# CONNECTOR.net
KiCad netlist of a schematic drawn in Altium Designer
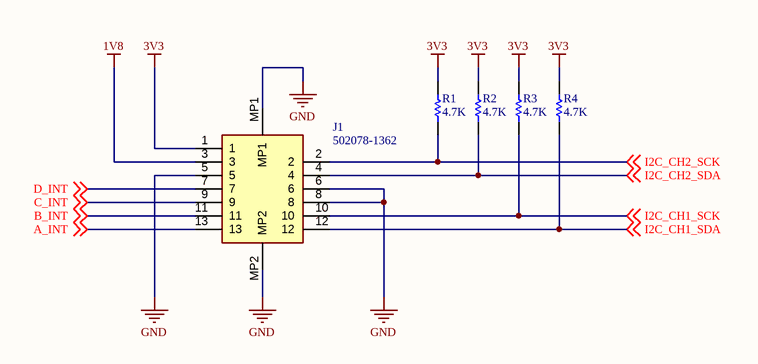
[diagram p0: CONNECTOR.SchDoc]

(export (version "E")
  (design (tool "Eeschema 10.0.6"))
  (components
    (comp (ref "J1")
      (value "502078-1362")
      (footprint "SamacSys:5020781362")
      (description "Connector")
      (fields (field (name "MOUSER PART NUMBER") "538-502078-1362"))
      (libsource (lib "*") (part "502078-1362"))
    )
    (comp (ref "R1")
      (value "4.7K")
      (footprint "RESC1005X40X25LL05T05")
      (description "Chip Resistor, 4.7 KOhm, +/- 1%, 0.1 W, -55 to 155 degC, 0402 (1005 Metric), RoHS, Tape and Reel")
      (fields (field (name "TOLERANCE") "1%") (field (name "PARTNUMBER") "ERJ-2RKF4701X"))
      (libsource (lib "Altium Content Vault") (part "RES-2"))
    )
    (comp (ref "R2")
      (value "4.7K")
      (footprint "RESC1005X40X25LL05T05")
      (description "Chip Resistor, 4.7 KOhm, +/- 1%, 0.1 W, -55 to 155 degC, 0402 (1005 Metric), RoHS, Tape and Reel")
      (fields (field (name "TOLERANCE") "1%") (field (name "PARTNUMBER") "ERJ-2RKF4701X"))
      (libsource (lib "Altium Content Vault") (part "RES-2"))
    )
    (comp (ref "R3")
      (value "4.7K")
      (footprint "RESC1005X40X25LL05T05")
      (description "Chip Resistor, 4.7 KOhm, +/- 1%, 0.1 W, -55 to 155 degC, 0402 (1005 Metric), RoHS, Tape and Reel")
      (fields (field (name "TOLERANCE") "1%") (field (name "PARTNUMBER") "ERJ-2RKF4701X"))
      (libsource (lib "Altium Content Vault") (part "RES-2"))
    )
    (comp (ref "R4")
      (value "4.7K")
      (footprint "RESC1005X40X25LL05T05")
      (description "Chip Resistor, 4.7 KOhm, +/- 1%, 0.1 W, -55 to 155 degC, 0402 (1005 Metric), RoHS, Tape and Reel")
      (fields (field (name "TOLERANCE") "1%") (field (name "PARTNUMBER") "ERJ-2RKF4701X"))
      (libsource (lib "Altium Content Vault") (part "RES-2"))
    )
  )
  (nets
    (net (code "1") (name "1V8") (class "Default")
      (node (ref "J1") (pin "3") (pinfunction "3_3") (pintype "passive"))
    )
    (net (code "2") (name "3V3") (class "Default")
      (node (ref "J1") (pin "1") (pinfunction "1_1") (pintype "passive"))
      (node (ref "R1") (pin "2") (pinfunction "2_2") (pintype "passive"))
      (node (ref "R2") (pin "2") (pinfunction "2_2") (pintype "passive"))
      (node (ref "R3") (pin "2") (pinfunction "2_2") (pintype "passive"))
      (node (ref "R4") (pin "2") (pinfunction "2_2") (pintype "passive"))
    )
    (net (code "3") (name "A_INT") (class "Default")
      (node (ref "J1") (pin "13") (pinfunction "13_13") (pintype "passive"))
    )
    (net (code "4") (name "B_INT") (class "Default")
      (node (ref "J1") (pin "11") (pinfunction "11_11") (pintype "passive"))
    )
    (net (code "5") (name "C_INT") (class "Default")
      (node (ref "J1") (pin "9") (pinfunction "9_9") (pintype "passive"))
    )
    (net (code "6") (name "D_INT") (class "Default")
      (node (ref "J1") (pin "7") (pinfunction "7_7") (pintype "passive"))
    )
    (net (code "7") (name "GND") (class "Default")
      (node (ref "J1") (pin "5") (pinfunction "5_5") (pintype "passive"))
      (node (ref "J1") (pin "6") (pinfunction "6_6") (pintype "passive"))
      (node (ref "J1") (pin "8") (pinfunction "8_8") (pintype "passive"))
      (node (ref "J1") (pin "MP1") (pinfunction "MP1_MP1") (pintype "passive"))
      (node (ref "J1") (pin "MP2") (pinfunction "MP2_MP2") (pintype "passive"))
    )
    (net (code "8") (name "I2C_CH1_SCK") (class "Default")
      (node (ref "J1") (pin "10") (pinfunction "10_10") (pintype "passive"))
      (node (ref "R3") (pin "1") (pinfunction "1_1") (pintype "passive"))
    )
    (net (code "9") (name "I2C_CH1_SDA") (class "Default")
      (node (ref "J1") (pin "12") (pinfunction "12_12") (pintype "passive"))
      (node (ref "R4") (pin "1") (pinfunction "1_1") (pintype "passive"))
    )
    (net (code "10") (name "I2C_CH2_SCK") (class "Default")
      (node (ref "J1") (pin "2") (pinfunction "2_2") (pintype "passive"))
      (node (ref "R1") (pin "1") (pinfunction "1_1") (pintype "passive"))
    )
    (net (code "11") (name "I2C_CH2_SDA") (class "Default")
      (node (ref "J1") (pin "4") (pinfunction "4_4") (pintype "passive"))
      (node (ref "R2") (pin "1") (pinfunction "1_1") (pintype "passive"))
    )
  )
)
